# SideYSolarPanel.net
KiCad netlist of a schematic drawn in EAGLE
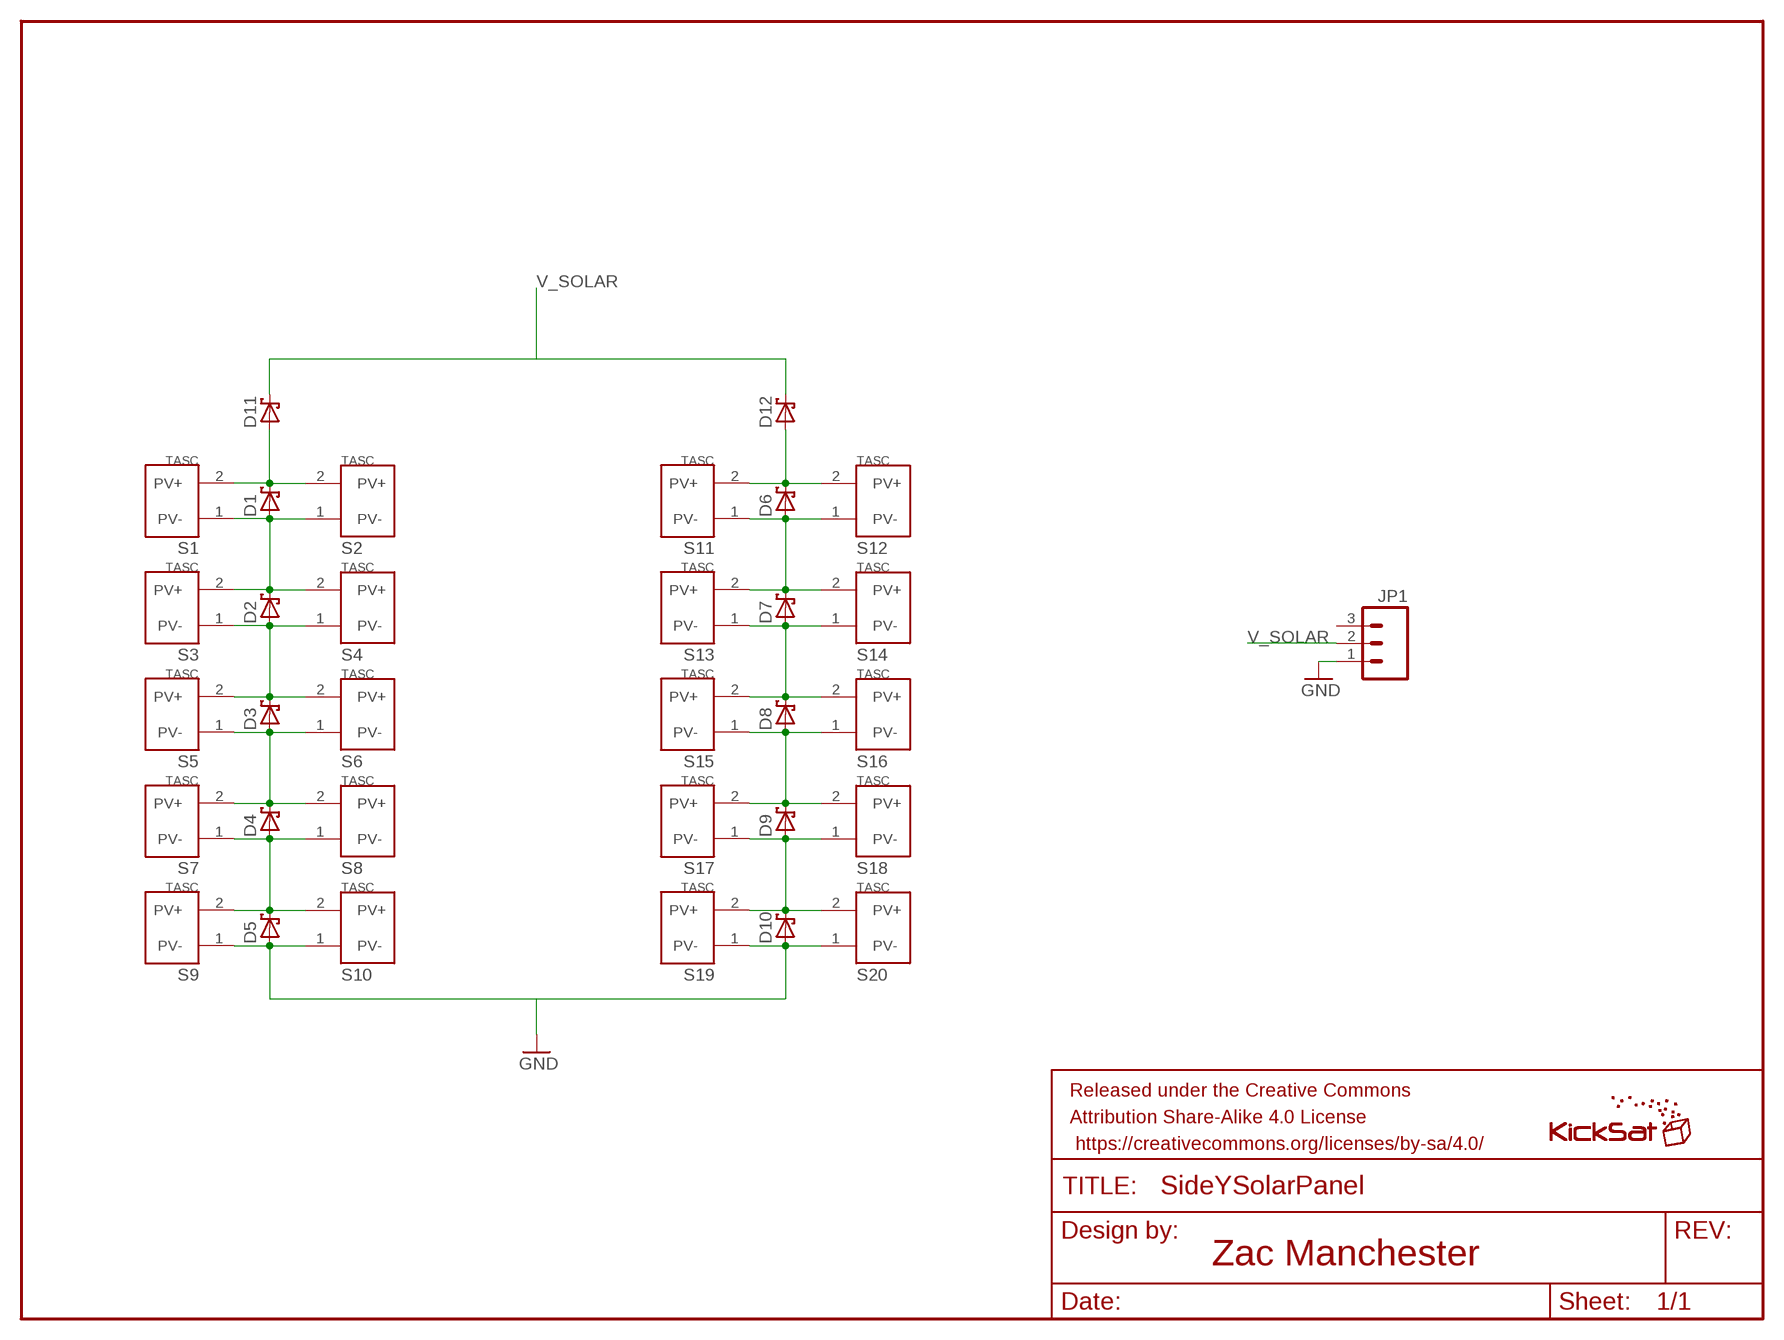
[diagram p0: schematic, sheet 1]

(export (version "E")
  (design (tool "Eeschema 10.0.6"))
  (components
    (comp (ref "D1")
      (value "SB_DIODE")
      (footprint "eagle-import:SB_DIODE")
      (libsource (lib "eagle-import") (part "SB_DIODE"))
    )
    (comp (ref "D2")
      (value "SB_DIODE")
      (footprint "eagle-import:SB_DIODE")
      (libsource (lib "eagle-import") (part "SB_DIODE"))
    )
    (comp (ref "D3")
      (value "SB_DIODE")
      (footprint "eagle-import:SB_DIODE")
      (libsource (lib "eagle-import") (part "SB_DIODE"))
    )
    (comp (ref "D4")
      (value "SB_DIODE")
      (footprint "eagle-import:SB_DIODE")
      (libsource (lib "eagle-import") (part "SB_DIODE"))
    )
    (comp (ref "D5")
      (value "SB_DIODE")
      (footprint "eagle-import:SB_DIODE")
      (libsource (lib "eagle-import") (part "SB_DIODE"))
    )
    (comp (ref "D6")
      (value "SB_DIODE")
      (footprint "eagle-import:SB_DIODE")
      (libsource (lib "eagle-import") (part "SB_DIODE"))
    )
    (comp (ref "D7")
      (value "SB_DIODE")
      (footprint "eagle-import:SB_DIODE")
      (libsource (lib "eagle-import") (part "SB_DIODE"))
    )
    (comp (ref "D8")
      (value "SB_DIODE")
      (footprint "eagle-import:SB_DIODE")
      (libsource (lib "eagle-import") (part "SB_DIODE"))
    )
    (comp (ref "D9")
      (value "SB_DIODE")
      (footprint "eagle-import:SB_DIODE")
      (libsource (lib "eagle-import") (part "SB_DIODE"))
    )
    (comp (ref "D10")
      (value "SB_DIODE")
      (footprint "eagle-import:SB_DIODE")
      (libsource (lib "eagle-import") (part "SB_DIODE"))
    )
    (comp (ref "D11")
      (value "SB_DIODE")
      (footprint "eagle-import:SB_DIODE")
      (libsource (lib "eagle-import") (part "SB_DIODE"))
    )
    (comp (ref "D12")
      (value "SB_DIODE")
      (footprint "eagle-import:SB_DIODE")
      (libsource (lib "eagle-import") (part "SB_DIODE"))
    )
    (comp (ref "FRAME1")
      (value "FRAME-LETTER")
      (footprint "eagle-import:CREATIVE_COMMONS")
      (libsource (lib "eagle-import") (part "FRAME-LETTER"))
    )
    (comp (ref "JP1")
      (value "M03POLAR_LOCK")
      (footprint "eagle-import:MOLEX-1X3_LOCK")
      (libsource (lib "eagle-import") (part "M03POLAR_LOCK"))
    )
    (comp (ref "S1")
      (value "SOLAR_CELL")
      (footprint "eagle-import:SOLAR_CELL")
      (libsource (lib "eagle-import") (part "SOLAR_CELL"))
    )
    (comp (ref "S2")
      (value "SOLAR_CELL")
      (footprint "eagle-import:SOLAR_CELL")
      (libsource (lib "eagle-import") (part "SOLAR_CELL"))
    )
    (comp (ref "S3")
      (value "SOLAR_CELL")
      (footprint "eagle-import:SOLAR_CELL")
      (libsource (lib "eagle-import") (part "SOLAR_CELL"))
    )
    (comp (ref "S4")
      (value "SOLAR_CELL")
      (footprint "eagle-import:SOLAR_CELL")
      (libsource (lib "eagle-import") (part "SOLAR_CELL"))
    )
    (comp (ref "S5")
      (value "SOLAR_CELL")
      (footprint "eagle-import:SOLAR_CELL")
      (libsource (lib "eagle-import") (part "SOLAR_CELL"))
    )
    (comp (ref "S6")
      (value "SOLAR_CELL")
      (footprint "eagle-import:SOLAR_CELL")
      (libsource (lib "eagle-import") (part "SOLAR_CELL"))
    )
    (comp (ref "S7")
      (value "SOLAR_CELL")
      (footprint "eagle-import:SOLAR_CELL")
      (libsource (lib "eagle-import") (part "SOLAR_CELL"))
    )
    (comp (ref "S8")
      (value "SOLAR_CELL")
      (footprint "eagle-import:SOLAR_CELL")
      (libsource (lib "eagle-import") (part "SOLAR_CELL"))
    )
    (comp (ref "S9")
      (value "SOLAR_CELL")
      (footprint "eagle-import:SOLAR_CELL")
      (libsource (lib "eagle-import") (part "SOLAR_CELL"))
    )
    (comp (ref "S10")
      (value "SOLAR_CELL")
      (footprint "eagle-import:SOLAR_CELL")
      (libsource (lib "eagle-import") (part "SOLAR_CELL"))
    )
    (comp (ref "S11")
      (value "SOLAR_CELL")
      (footprint "eagle-import:SOLAR_CELL")
      (libsource (lib "eagle-import") (part "SOLAR_CELL"))
    )
    (comp (ref "S12")
      (value "SOLAR_CELL")
      (footprint "eagle-import:SOLAR_CELL")
      (libsource (lib "eagle-import") (part "SOLAR_CELL"))
    )
    (comp (ref "S13")
      (value "SOLAR_CELL")
      (footprint "eagle-import:SOLAR_CELL")
      (libsource (lib "eagle-import") (part "SOLAR_CELL"))
    )
    (comp (ref "S14")
      (value "SOLAR_CELL")
      (footprint "eagle-import:SOLAR_CELL")
      (libsource (lib "eagle-import") (part "SOLAR_CELL"))
    )
    (comp (ref "S15")
      (value "SOLAR_CELL")
      (footprint "eagle-import:SOLAR_CELL")
      (libsource (lib "eagle-import") (part "SOLAR_CELL"))
    )
    (comp (ref "S16")
      (value "SOLAR_CELL")
      (footprint "eagle-import:SOLAR_CELL")
      (libsource (lib "eagle-import") (part "SOLAR_CELL"))
    )
    (comp (ref "S17")
      (value "SOLAR_CELL")
      (footprint "eagle-import:SOLAR_CELL")
      (libsource (lib "eagle-import") (part "SOLAR_CELL"))
    )
    (comp (ref "S18")
      (value "SOLAR_CELL")
      (footprint "eagle-import:SOLAR_CELL")
      (libsource (lib "eagle-import") (part "SOLAR_CELL"))
    )
    (comp (ref "S19")
      (value "SOLAR_CELL")
      (footprint "eagle-import:SOLAR_CELL")
      (libsource (lib "eagle-import") (part "SOLAR_CELL"))
    )
    (comp (ref "S20")
      (value "SOLAR_CELL")
      (footprint "eagle-import:SOLAR_CELL")
      (libsource (lib "eagle-import") (part "SOLAR_CELL"))
    )
    (comp (ref "U$1")
      (value "KICKSAT_LOGO")
      (footprint "eagle-import:KICKSAT_LOGO")
      (libsource (lib "eagle-import") (part "KICKSAT_LOGO"))
    )
  )
  (nets
    (net (code "1") (name "/V_SOLAR") (class "Default")
      (node (ref "D11") (pin "NEG") (pinfunction "NEG_NEG") (pintype "passive"))
      (node (ref "D12") (pin "NEG") (pinfunction "NEG_NEG") (pintype "passive"))
      (node (ref "JP1") (pin "2") (pinfunction "2_2") (pintype "passive"))
    )
    (net (code "2") (name "GND") (class "Default")
      (node (ref "D10") (pin "POS") (pinfunction "POS_POS") (pintype "passive"))
      (node (ref "D5") (pin "POS") (pinfunction "POS_POS") (pintype "passive"))
      (node (ref "JP1") (pin "1") (pinfunction "1_1") (pintype "passive"))
      (node (ref "S10") (pin "1") (pinfunction "PV-_1") (pintype "bidirectional"))
      (node (ref "S19") (pin "1") (pinfunction "PV-_1") (pintype "bidirectional"))
      (node (ref "S20") (pin "1") (pinfunction "PV-_1") (pintype "bidirectional"))
      (node (ref "S9") (pin "1") (pinfunction "PV-_1") (pintype "bidirectional"))
    )
    (net (code "3") (name "Net-(S1-PV+)") (class "Default")
      (node (ref "D1") (pin "NEG") (pinfunction "NEG_NEG") (pintype "passive"))
      (node (ref "D11") (pin "POS") (pinfunction "POS_POS") (pintype "passive"))
      (node (ref "S1") (pin "2") (pinfunction "PV+_2") (pintype "bidirectional"))
      (node (ref "S2") (pin "2") (pinfunction "PV+_2") (pintype "bidirectional"))
    )
    (net (code "4") (name "Net-(S1-PV-)") (class "Default")
      (node (ref "D1") (pin "POS") (pinfunction "POS_POS") (pintype "passive"))
      (node (ref "D2") (pin "NEG") (pinfunction "NEG_NEG") (pintype "passive"))
      (node (ref "S1") (pin "1") (pinfunction "PV-_1") (pintype "bidirectional"))
      (node (ref "S2") (pin "1") (pinfunction "PV-_1") (pintype "bidirectional"))
      (node (ref "S3") (pin "2") (pinfunction "PV+_2") (pintype "bidirectional"))
      (node (ref "S4") (pin "2") (pinfunction "PV+_2") (pintype "bidirectional"))
    )
    (net (code "5") (name "Net-(S3-PV-)") (class "Default")
      (node (ref "D2") (pin "POS") (pinfunction "POS_POS") (pintype "passive"))
      (node (ref "D3") (pin "NEG") (pinfunction "NEG_NEG") (pintype "passive"))
      (node (ref "S3") (pin "1") (pinfunction "PV-_1") (pintype "bidirectional"))
      (node (ref "S4") (pin "1") (pinfunction "PV-_1") (pintype "bidirectional"))
      (node (ref "S5") (pin "2") (pinfunction "PV+_2") (pintype "bidirectional"))
      (node (ref "S6") (pin "2") (pinfunction "PV+_2") (pintype "bidirectional"))
    )
    (net (code "6") (name "Net-(S5-PV-)") (class "Default")
      (node (ref "D3") (pin "POS") (pinfunction "POS_POS") (pintype "passive"))
      (node (ref "D4") (pin "NEG") (pinfunction "NEG_NEG") (pintype "passive"))
      (node (ref "S5") (pin "1") (pinfunction "PV-_1") (pintype "bidirectional"))
      (node (ref "S6") (pin "1") (pinfunction "PV-_1") (pintype "bidirectional"))
      (node (ref "S7") (pin "2") (pinfunction "PV+_2") (pintype "bidirectional"))
      (node (ref "S8") (pin "2") (pinfunction "PV+_2") (pintype "bidirectional"))
    )
    (net (code "7") (name "Net-(S10-PV+)") (class "Default")
      (node (ref "D4") (pin "POS") (pinfunction "POS_POS") (pintype "passive"))
      (node (ref "D5") (pin "NEG") (pinfunction "NEG_NEG") (pintype "passive"))
      (node (ref "S10") (pin "2") (pinfunction "PV+_2") (pintype "bidirectional"))
      (node (ref "S7") (pin "1") (pinfunction "PV-_1") (pintype "bidirectional"))
      (node (ref "S8") (pin "1") (pinfunction "PV-_1") (pintype "bidirectional"))
      (node (ref "S9") (pin "2") (pinfunction "PV+_2") (pintype "bidirectional"))
    )
    (net (code "8") (name "Net-(S11-PV+)") (class "Default")
      (node (ref "D12") (pin "POS") (pinfunction "POS_POS") (pintype "passive"))
      (node (ref "D6") (pin "NEG") (pinfunction "NEG_NEG") (pintype "passive"))
      (node (ref "S11") (pin "2") (pinfunction "PV+_2") (pintype "bidirectional"))
      (node (ref "S12") (pin "2") (pinfunction "PV+_2") (pintype "bidirectional"))
    )
    (net (code "9") (name "Net-(S11-PV-)") (class "Default")
      (node (ref "D6") (pin "POS") (pinfunction "POS_POS") (pintype "passive"))
      (node (ref "D7") (pin "NEG") (pinfunction "NEG_NEG") (pintype "passive"))
      (node (ref "S11") (pin "1") (pinfunction "PV-_1") (pintype "bidirectional"))
      (node (ref "S12") (pin "1") (pinfunction "PV-_1") (pintype "bidirectional"))
      (node (ref "S13") (pin "2") (pinfunction "PV+_2") (pintype "bidirectional"))
      (node (ref "S14") (pin "2") (pinfunction "PV+_2") (pintype "bidirectional"))
    )
    (net (code "10") (name "Net-(S13-PV-)") (class "Default")
      (node (ref "D7") (pin "POS") (pinfunction "POS_POS") (pintype "passive"))
      (node (ref "D8") (pin "NEG") (pinfunction "NEG_NEG") (pintype "passive"))
      (node (ref "S13") (pin "1") (pinfunction "PV-_1") (pintype "bidirectional"))
      (node (ref "S14") (pin "1") (pinfunction "PV-_1") (pintype "bidirectional"))
      (node (ref "S15") (pin "2") (pinfunction "PV+_2") (pintype "bidirectional"))
      (node (ref "S16") (pin "2") (pinfunction "PV+_2") (pintype "bidirectional"))
    )
    (net (code "11") (name "Net-(S15-PV-)") (class "Default")
      (node (ref "D8") (pin "POS") (pinfunction "POS_POS") (pintype "passive"))
      (node (ref "D9") (pin "NEG") (pinfunction "NEG_NEG") (pintype "passive"))
      (node (ref "S15") (pin "1") (pinfunction "PV-_1") (pintype "bidirectional"))
      (node (ref "S16") (pin "1") (pinfunction "PV-_1") (pintype "bidirectional"))
      (node (ref "S17") (pin "2") (pinfunction "PV+_2") (pintype "bidirectional"))
      (node (ref "S18") (pin "2") (pinfunction "PV+_2") (pintype "bidirectional"))
    )
    (net (code "12") (name "Net-(S17-PV-)") (class "Default")
      (node (ref "D10") (pin "NEG") (pinfunction "NEG_NEG") (pintype "passive"))
      (node (ref "D9") (pin "POS") (pinfunction "POS_POS") (pintype "passive"))
      (node (ref "S17") (pin "1") (pinfunction "PV-_1") (pintype "bidirectional"))
      (node (ref "S18") (pin "1") (pinfunction "PV-_1") (pintype "bidirectional"))
      (node (ref "S19") (pin "2") (pinfunction "PV+_2") (pintype "bidirectional"))
      (node (ref "S20") (pin "2") (pinfunction "PV+_2") (pintype "bidirectional"))
    )
    (net (code "13") (name "unconnected-(JP1-Pad3)") (class "Default")
      (node (ref "JP1") (pin "3") (pinfunction "3_3") (pintype "passive"))
    )
  )
)
